# RPI4Soar_V1.net
KiCad netlist of a schematic drawn in EAGLE
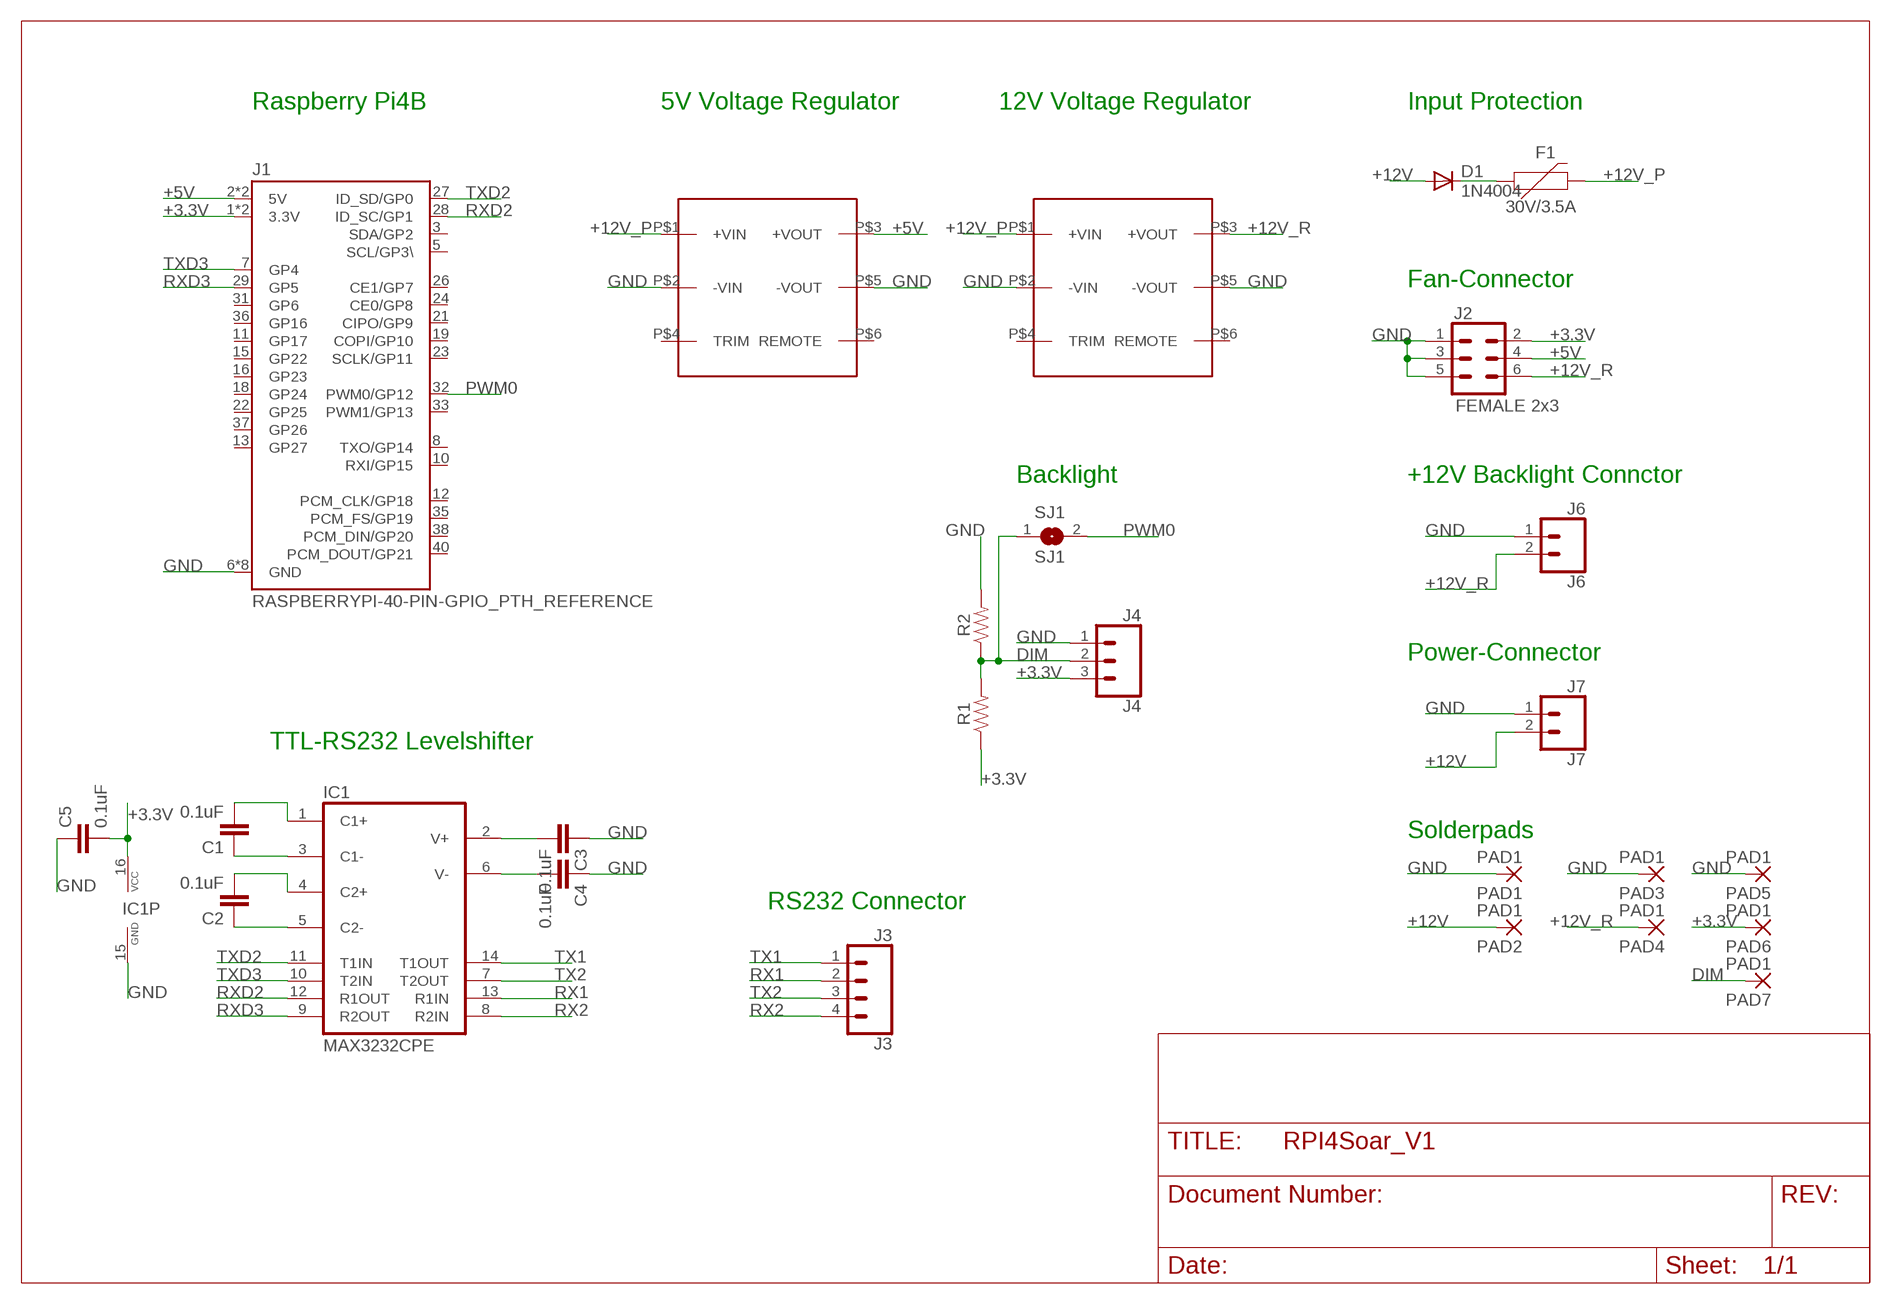
[diagram p0: schematic, sheet 1]

(export (version "E")
  (design (tool "Eeschema 10.0.6"))
  (components
    (comp (ref "C1")
      (value "0.1uF")
      (footprint "eagle-import:CAP-PTH-SMALL-KIT")
      (libsource (lib "eagle-import") (part "0.1UF-KIT-EZ-50V-20%"))
    )
    (comp (ref "C2")
      (value "0.1uF")
      (footprint "eagle-import:CAP-PTH-SMALL-KIT")
      (libsource (lib "eagle-import") (part "0.1UF-KIT-EZ-50V-20%"))
    )
    (comp (ref "C3")
      (value "0.1uF")
      (footprint "eagle-import:CAP-PTH-SMALL-KIT")
      (libsource (lib "eagle-import") (part "0.1UF-KIT-EZ-50V-20%"))
    )
    (comp (ref "C4")
      (value "0.1uF")
      (footprint "eagle-import:CAP-PTH-SMALL-KIT")
      (libsource (lib "eagle-import") (part "0.1UF-KIT-EZ-50V-20%"))
    )
    (comp (ref "C5")
      (value "0.1uF")
      (footprint "eagle-import:CAP-PTH-SMALL-KIT")
      (libsource (lib "eagle-import") (part "0.1UF-KIT-EZ-50V-20%"))
    )
    (comp (ref "D1")
      (value "1N4004")
      (footprint "eagle-import:DO41-10")
      (libsource (lib "eagle-import") (part "1N4004"))
    )
    (comp (ref "F1")
      (value "30V/3.5A")
      (footprint "eagle-import:PTH")
      (libsource (lib "eagle-import") (part "PPTC_PTH"))
    )
    (comp (ref "IC1")
      (value "MAX3232CPE")
      (footprint "eagle-import:DIL16")
      (fields (field (name "MF") "MAXIM") (field (name "MPN") "MAX3232CPE+") (field (name "SPICEPREFIX") "X"))
      (libsource (lib "eagle-import") (part "MAX3232PEC"))
    )
    (comp (ref "J1")
      (value "RASPBERRYPI-40-PIN-GPIO_PTH_REFERENCE")
      (footprint "eagle-import:RASPBERRY_PI_HAT_40_PIN_PTH_WITH_REFERNCE")
      (libsource (lib "eagle-import") (part "RASPBERRYPI-40-PIN-GPIO_PTH_REFERENCE"))
    )
    (comp (ref "J2")
      (value "FEMALE 2x3")
      (footprint "eagle-import:2X3")
      (libsource (lib "eagle-import") (part "CONN_03X2FEMALE"))
    )
    (comp (ref "J3")
      (value "J3")
      (footprint "eagle-import:1X04")
      (libsource (lib "eagle-import") (part "CONN_04PTH"))
    )
    (comp (ref "J4")
      (value "J4")
      (footprint "eagle-import:1X03")
      (libsource (lib "eagle-import") (part "CONN_03"))
    )
    (comp (ref "J6")
      (value "J6")
      (footprint "eagle-import:1X02")
      (libsource (lib "eagle-import") (part "CONN_02"))
    )
    (comp (ref "J7")
      (value "J7")
      (footprint "eagle-import:1X02")
      (libsource (lib "eagle-import") (part "CONN_02"))
    )
    (comp (ref "PAD1")
      (value "PAD1")
      (footprint "eagle-import:SMD2,54-5,08")
      (libsource (lib "eagle-import") (part "SMD5"))
    )
    (comp (ref "PAD2")
      (value "PAD1")
      (footprint "eagle-import:SMD2,54-5,08")
      (libsource (lib "eagle-import") (part "SMD5"))
    )
    (comp (ref "PAD3")
      (value "PAD1")
      (footprint "eagle-import:SMD2,54-5,08")
      (libsource (lib "eagle-import") (part "SMD5"))
    )
    (comp (ref "PAD4")
      (value "PAD1")
      (footprint "eagle-import:SMD2,54-5,08")
      (libsource (lib "eagle-import") (part "SMD5"))
    )
    (comp (ref "PAD5")
      (value "PAD1")
      (footprint "eagle-import:SMD2,54-5,08")
      (libsource (lib "eagle-import") (part "SMD5"))
    )
    (comp (ref "PAD6")
      (value "PAD1")
      (footprint "eagle-import:SMD2,54-5,08")
      (libsource (lib "eagle-import") (part "SMD5"))
    )
    (comp (ref "PAD7")
      (value "PAD1")
      (footprint "eagle-import:SMD2,54-5,08")
      (libsource (lib "eagle-import") (part "SMD5"))
    )
    (comp (ref "R1")
      (value "RESISTORAXIAL-0.3")
      (footprint "eagle-import:AXIAL-0.3")
      (libsource (lib "eagle-import") (part "RESISTORAXIAL-0.3"))
    )
    (comp (ref "R2")
      (value "RESISTORAXIAL-0.3")
      (footprint "eagle-import:AXIAL-0.3")
      (libsource (lib "eagle-import") (part "RESISTORAXIAL-0.3"))
    )
    (comp (ref "SJ1")
      (value "SJ1")
      (footprint "eagle-import:SJ")
      (libsource (lib "eagle-import") (part "SJ"))
    )
    (comp (ref "U$1")
      (value "TRACO_THN15WI +5V")
      (footprint "eagle-import:TRACO_THN15WI")
      (libsource (lib "eagle-import") (part "TRACO_THN15WI"))
    )
    (comp (ref "U$2")
      (value "TRACO_THN15WI +12V")
      (footprint "eagle-import:TRACO_THN15WI")
      (libsource (lib "eagle-import") (part "TRACO_THN15WI"))
    )
  )
  (nets
    (net (code "1") (name "/+3.3V") (class "Default")
      (node (ref "C5") (pin "2") (pinfunction "2_2") (pintype "passive"))
      (node (ref "IC1") (pin "16") (pinfunction "VCC_16") (pintype "power_in"))
      (node (ref "J1") (pin "1") (pinfunction "3.3V_1") (pintype "power_in"))
      (node (ref "J1") (pin "17") (pinfunction "3.3V_17") (pintype "power_in"))
      (node (ref "J2") (pin "2") (pinfunction "2_2") (pintype "bidirectional"))
      (node (ref "J4") (pin "3") (pinfunction "3_3") (pintype "passive"))
      (node (ref "PAD6") (pin "1") (pinfunction "P_1") (pintype "passive"))
      (node (ref "R1") (pin "P$1") (pinfunction "1_P$1") (pintype "passive"))
    )
    (net (code "2") (name "/+5V") (class "Default")
      (node (ref "J1") (pin "2") (pinfunction "5V_2") (pintype "power_in"))
      (node (ref "J1") (pin "4") (pinfunction "5V_4") (pintype "power_in"))
      (node (ref "J2") (pin "4") (pinfunction "4_4") (pintype "bidirectional"))
      (node (ref "U$1") (pin "P$3") (pinfunction "+VOUT_P$3") (pintype "bidirectional"))
    )
    (net (code "3") (name "/+12V") (class "Default")
      (node (ref "D1") (pin "A") (pinfunction "A_A") (pintype "passive"))
      (node (ref "J7") (pin "2") (pinfunction "2_2") (pintype "passive"))
      (node (ref "PAD2") (pin "1") (pinfunction "P_1") (pintype "passive"))
    )
    (net (code "4") (name "/+12V_P") (class "Default")
      (node (ref "F1") (pin "P$2") (pinfunction "2_P$2") (pintype "bidirectional"))
      (node (ref "U$1") (pin "P$1") (pinfunction "+VIN_P$1") (pintype "bidirectional"))
      (node (ref "U$2") (pin "P$1") (pinfunction "+VIN_P$1") (pintype "bidirectional"))
    )
    (net (code "5") (name "/+12V_R") (class "Default")
      (node (ref "J2") (pin "6") (pinfunction "6_6") (pintype "bidirectional"))
      (node (ref "J6") (pin "2") (pinfunction "2_2") (pintype "passive"))
      (node (ref "PAD4") (pin "1") (pinfunction "P_1") (pintype "passive"))
      (node (ref "U$2") (pin "P$3") (pinfunction "+VOUT_P$3") (pintype "bidirectional"))
    )
    (net (code "6") (name "/DIM") (class "Default")
      (node (ref "J4") (pin "2") (pinfunction "2_2") (pintype "passive"))
      (node (ref "PAD7") (pin "1") (pinfunction "P_1") (pintype "passive"))
      (node (ref "R1") (pin "P$2") (pinfunction "2_P$2") (pintype "passive"))
      (node (ref "R2") (pin "P$1") (pinfunction "1_P$1") (pintype "passive"))
      (node (ref "SJ1") (pin "1") (pinfunction "1_1") (pintype "passive"))
    )
    (net (code "7") (name "/GND") (class "Default")
      (node (ref "C3") (pin "1") (pinfunction "1_1") (pintype "passive"))
      (node (ref "C4") (pin "1") (pinfunction "1_1") (pintype "passive"))
      (node (ref "C5") (pin "1") (pinfunction "1_1") (pintype "passive"))
      (node (ref "IC1") (pin "15") (pinfunction "GND_15") (pintype "power_in"))
      (node (ref "J1") (pin "14") (pinfunction "GND_14") (pintype "power_in"))
      (node (ref "J1") (pin "20") (pinfunction "GND_20") (pintype "power_in"))
      (node (ref "J1") (pin "25") (pinfunction "GND_25") (pintype "power_in"))
      (node (ref "J1") (pin "30") (pinfunction "GND_30") (pintype "power_in"))
      (node (ref "J1") (pin "34") (pinfunction "GND_34") (pintype "power_in"))
      (node (ref "J1") (pin "39") (pinfunction "GND_39") (pintype "power_in"))
      (node (ref "J1") (pin "6") (pinfunction "GND_6") (pintype "power_in"))
      (node (ref "J1") (pin "9") (pinfunction "GND_9") (pintype "power_in"))
      (node (ref "J2") (pin "1") (pinfunction "1_1") (pintype "bidirectional"))
      (node (ref "J2") (pin "3") (pinfunction "3_3") (pintype "bidirectional"))
      (node (ref "J2") (pin "5") (pinfunction "5_5") (pintype "bidirectional"))
      (node (ref "J4") (pin "1") (pinfunction "1_1") (pintype "passive"))
      (node (ref "J6") (pin "1") (pinfunction "1_1") (pintype "passive"))
      (node (ref "J7") (pin "1") (pinfunction "1_1") (pintype "passive"))
      (node (ref "PAD1") (pin "1") (pinfunction "P_1") (pintype "passive"))
      (node (ref "PAD3") (pin "1") (pinfunction "P_1") (pintype "passive"))
      (node (ref "PAD5") (pin "1") (pinfunction "P_1") (pintype "passive"))
      (node (ref "R2") (pin "P$2") (pinfunction "2_P$2") (pintype "passive"))
      (node (ref "U$1") (pin "P$2") (pinfunction "-VIN_P$2") (pintype "bidirectional"))
      (node (ref "U$1") (pin "P$5") (pinfunction "-VOUT_P$5") (pintype "bidirectional"))
      (node (ref "U$2") (pin "P$2") (pinfunction "-VIN_P$2") (pintype "bidirectional"))
      (node (ref "U$2") (pin "P$5") (pinfunction "-VOUT_P$5") (pintype "bidirectional"))
    )
    (net (code "8") (name "/PWM0") (class "Default")
      (node (ref "J1") (pin "32") (pinfunction "PWM0/GP12_32") (pintype "bidirectional"))
      (node (ref "SJ1") (pin "2") (pinfunction "2_2") (pintype "passive"))
    )
    (net (code "9") (name "/RX1") (class "Default")
      (node (ref "IC1") (pin "13") (pinfunction "R1IN_13") (pintype "input"))
      (node (ref "J3") (pin "2") (pinfunction "2_2") (pintype "passive"))
    )
    (net (code "10") (name "/RX2") (class "Default")
      (node (ref "IC1") (pin "8") (pinfunction "R2IN_8") (pintype "input"))
      (node (ref "J3") (pin "4") (pinfunction "4_4") (pintype "passive"))
    )
    (net (code "11") (name "/RXD2") (class "Default")
      (node (ref "IC1") (pin "12") (pinfunction "R1OUT_12") (pintype "output"))
      (node (ref "J1") (pin "28") (pinfunction "ID_SC/GP1_28") (pintype "bidirectional"))
    )
    (net (code "12") (name "/RXD3") (class "Default")
      (node (ref "IC1") (pin "9") (pinfunction "R2OUT_9") (pintype "output"))
      (node (ref "J1") (pin "29") (pinfunction "GP5_29") (pintype "bidirectional"))
    )
    (net (code "13") (name "/TX1") (class "Default")
      (node (ref "IC1") (pin "14") (pinfunction "T1OUT_14") (pintype "output"))
      (node (ref "J3") (pin "1") (pinfunction "1_1") (pintype "passive"))
    )
    (net (code "14") (name "/TX2") (class "Default")
      (node (ref "IC1") (pin "7") (pinfunction "T2OUT_7") (pintype "output"))
      (node (ref "J3") (pin "3") (pinfunction "3_3") (pintype "passive"))
    )
    (net (code "15") (name "/TXD2") (class "Default")
      (node (ref "IC1") (pin "11") (pinfunction "T1IN_11") (pintype "input"))
      (node (ref "J1") (pin "27") (pinfunction "ID_SD/GP0_27") (pintype "bidirectional"))
    )
    (net (code "16") (name "/TXD3") (class "Default")
      (node (ref "IC1") (pin "10") (pinfunction "T2IN_10") (pintype "input"))
      (node (ref "J1") (pin "7") (pinfunction "GP4_7") (pintype "bidirectional"))
    )
    (net (code "17") (name "Net-(F1-1)") (class "Default")
      (node (ref "D1") (pin "C") (pinfunction "C_C") (pintype "passive"))
      (node (ref "F1") (pin "P$1") (pinfunction "1_P$1") (pintype "bidirectional"))
    )
    (net (code "18") (name "Net-(IC1A-C1+)") (class "Default")
      (node (ref "C1") (pin "2") (pinfunction "2_2") (pintype "passive"))
      (node (ref "IC1") (pin "1") (pinfunction "C1+_1") (pintype "bidirectional"))
    )
    (net (code "19") (name "Net-(IC1A-C1-)") (class "Default")
      (node (ref "C1") (pin "1") (pinfunction "1_1") (pintype "passive"))
      (node (ref "IC1") (pin "3") (pinfunction "C1-_3") (pintype "bidirectional"))
    )
    (net (code "20") (name "Net-(IC1A-C2+)") (class "Default")
      (node (ref "C2") (pin "2") (pinfunction "2_2") (pintype "passive"))
      (node (ref "IC1") (pin "4") (pinfunction "C2+_4") (pintype "bidirectional"))
    )
    (net (code "21") (name "Net-(IC1A-C2-)") (class "Default")
      (node (ref "C2") (pin "1") (pinfunction "1_1") (pintype "passive"))
      (node (ref "IC1") (pin "5") (pinfunction "C2-_5") (pintype "bidirectional"))
    )
    (net (code "22") (name "Net-(IC1A-V+)") (class "Default")
      (node (ref "C3") (pin "2") (pinfunction "2_2") (pintype "passive"))
      (node (ref "IC1") (pin "2") (pinfunction "V+_2") (pintype "bidirectional"))
    )
    (net (code "23") (name "Net-(IC1A-V-)") (class "Default")
      (node (ref "C4") (pin "2") (pinfunction "2_2") (pintype "passive"))
      (node (ref "IC1") (pin "6") (pinfunction "V-_6") (pintype "bidirectional"))
    )
    (net (code "24") (name "unconnected-(J1-CE0{slash}GP8-Pad24)") (class "Default")
      (node (ref "J1") (pin "24") (pinfunction "CE0/GP8_24") (pintype "output"))
    )
    (net (code "25") (name "unconnected-(J1-CE1{slash}GP7-Pad26)") (class "Default")
      (node (ref "J1") (pin "26") (pinfunction "CE1/GP7_26") (pintype "output"))
    )
    (net (code "26") (name "unconnected-(J1-CIPO{slash}GP9-Pad21)") (class "Default")
      (node (ref "J1") (pin "21") (pinfunction "CIPO/GP9_21") (pintype "input"))
    )
    (net (code "27") (name "unconnected-(J1-COPI{slash}GP10-Pad19)") (class "Default")
      (node (ref "J1") (pin "19") (pinfunction "COPI/GP10_19") (pintype "output"))
    )
    (net (code "28") (name "unconnected-(J1-GP6-Pad31)") (class "Default")
      (node (ref "J1") (pin "31") (pinfunction "GP6_31") (pintype "bidirectional"))
    )
    (net (code "29") (name "unconnected-(J1-GP16-Pad36)") (class "Default")
      (node (ref "J1") (pin "36") (pinfunction "GP16_36") (pintype "bidirectional"))
    )
    (net (code "30") (name "unconnected-(J1-GP17-Pad11)") (class "Default")
      (node (ref "J1") (pin "11") (pinfunction "GP17_11") (pintype "bidirectional"))
    )
    (net (code "31") (name "unconnected-(J1-GP22-Pad15)") (class "Default")
      (node (ref "J1") (pin "15") (pinfunction "GP22_15") (pintype "bidirectional"))
    )
    (net (code "32") (name "unconnected-(J1-GP23-Pad16)") (class "Default")
      (node (ref "J1") (pin "16") (pinfunction "GP23_16") (pintype "bidirectional"))
    )
    (net (code "33") (name "unconnected-(J1-GP24-Pad18)") (class "Default")
      (node (ref "J1") (pin "18") (pinfunction "GP24_18") (pintype "bidirectional"))
    )
    (net (code "34") (name "unconnected-(J1-GP25-Pad22)") (class "Default")
      (node (ref "J1") (pin "22") (pinfunction "GP25_22") (pintype "bidirectional"))
    )
    (net (code "35") (name "unconnected-(J1-GP26-Pad37)") (class "Default")
      (node (ref "J1") (pin "37") (pinfunction "GP26_37") (pintype "bidirectional"))
    )
    (net (code "36") (name "unconnected-(J1-GP27-Pad13)") (class "Default")
      (node (ref "J1") (pin "13") (pinfunction "GP27_13") (pintype "bidirectional"))
    )
    (net (code "37") (name "unconnected-(J1-PCM_CLK{slash}GP18-Pad12)") (class "Default")
      (node (ref "J1") (pin "12") (pinfunction "PCM_CLK/GP18_12") (pintype "bidirectional"))
    )
    (net (code "38") (name "unconnected-(J1-PCM_DIN{slash}GP20-Pad38)") (class "Default")
      (node (ref "J1") (pin "38") (pinfunction "PCM_DIN/GP20_38") (pintype "bidirectional"))
    )
    (net (code "39") (name "unconnected-(J1-PCM_DOUT{slash}GP21-Pad40)") (class "Default")
      (node (ref "J1") (pin "40") (pinfunction "PCM_DOUT/GP21_40") (pintype "bidirectional"))
    )
    (net (code "40") (name "unconnected-(J1-PCM_FS{slash}GP19-Pad35)") (class "Default")
      (node (ref "J1") (pin "35") (pinfunction "PCM_FS/GP19_35") (pintype "bidirectional"))
    )
    (net (code "41") (name "unconnected-(J1-PWM1{slash}GP13-Pad33)") (class "Default")
      (node (ref "J1") (pin "33") (pinfunction "PWM1/GP13_33") (pintype "bidirectional"))
    )
    (net (code "42") (name "unconnected-(J1-RXI{slash}GP15-Pad10)") (class "Default")
      (node (ref "J1") (pin "10") (pinfunction "RXI/GP15_10") (pintype "input"))
    )
    (net (code "43") (name "unconnected-(J1-SCLK{slash}GP11-Pad23)") (class "Default")
      (node (ref "J1") (pin "23") (pinfunction "SCLK/GP11_23") (pintype "output"))
    )
    (net (code "44") (name "unconnected-(J1-SCL{slash}GP3\\-Pad5)") (class "Default")
      (node (ref "J1") (pin "5") (pinfunction "SCL/GP3\\_5") (pintype "bidirectional"))
    )
    (net (code "45") (name "unconnected-(J1-SDA{slash}GP2-Pad3)") (class "Default")
      (node (ref "J1") (pin "3") (pinfunction "SDA/GP2_3") (pintype "bidirectional"))
    )
    (net (code "46") (name "unconnected-(J1-TXO{slash}GP14-Pad8)") (class "Default")
      (node (ref "J1") (pin "8") (pinfunction "TXO/GP14_8") (pintype "output"))
    )
    (net (code "47") (name "unconnected-(U$1-REMOTE-PadP$6)") (class "Default")
      (node (ref "U$1") (pin "P$6") (pinfunction "REMOTE_P$6") (pintype "bidirectional"))
    )
    (net (code "48") (name "unconnected-(U$1-TRIM-PadP$4)") (class "Default")
      (node (ref "U$1") (pin "P$4") (pinfunction "TRIM_P$4") (pintype "bidirectional"))
    )
    (net (code "49") (name "unconnected-(U$2-REMOTE-PadP$6)") (class "Default")
      (node (ref "U$2") (pin "P$6") (pinfunction "REMOTE_P$6") (pintype "bidirectional"))
    )
    (net (code "50") (name "unconnected-(U$2-TRIM-PadP$4)") (class "Default")
      (node (ref "U$2") (pin "P$4") (pinfunction "TRIM_P$4") (pintype "bidirectional"))
    )
  )
)
